# dCompass_7.net
KiCad netlist of a schematic drawn in EAGLE
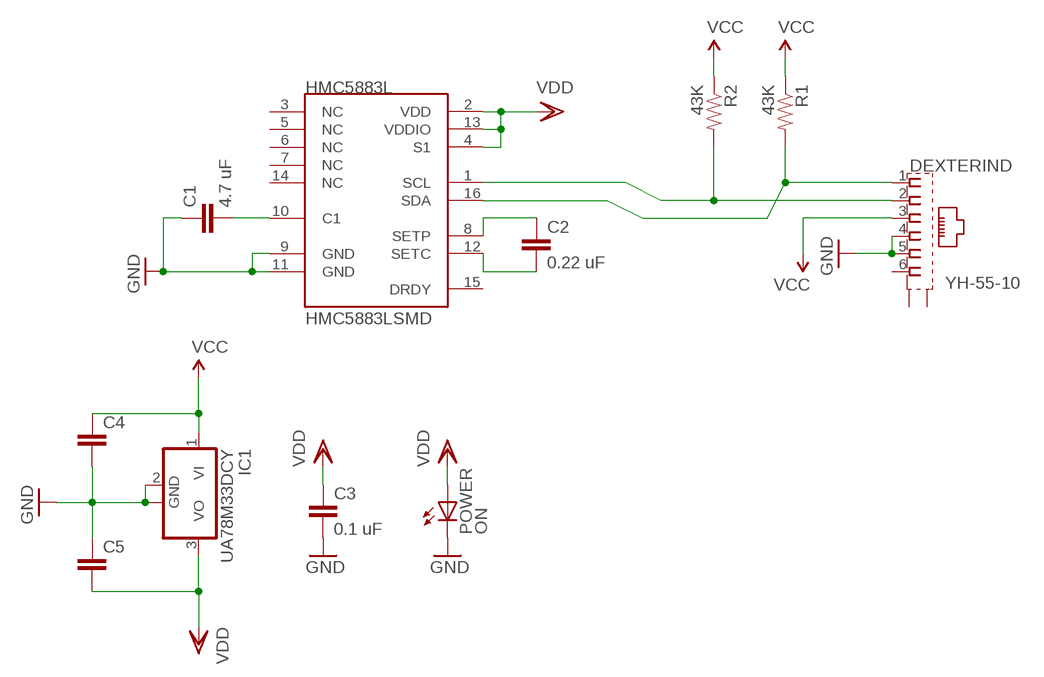
[diagram p0: schematic, sheet 1]

(export (version "E")
  (design (tool "Eeschema 10.0.6"))
  (components
    (comp (ref "C1")
      (value "4.7 uF")
      (footprint "eagle-import:0805")
      (libsource (lib "eagle-import") (part "CAP0805"))
    )
    (comp (ref "C2")
      (value "0.22 uF")
      (footprint "eagle-import:0805")
      (libsource (lib "eagle-import") (part "CAP0805"))
    )
    (comp (ref "C3")
      (value "0.1 uF")
      (footprint "eagle-import:0805")
      (libsource (lib "eagle-import") (part "CAP0805"))
    )
    (comp (ref "C4")
      (value "CAP0805")
      (footprint "eagle-import:0805")
      (libsource (lib "eagle-import") (part "CAP0805"))
    )
    (comp (ref "C5")
      (value "CAP0805")
      (footprint "eagle-import:0805")
      (libsource (lib "eagle-import") (part "CAP0805"))
    )
    (comp (ref "DEXTERIND")
      (value "YH-55-10")
      (footprint "eagle-import:YH-55-10")
      (libsource (lib "eagle-import") (part "YH-55-10"))
    )
    (comp (ref "HMC5883L")
      (value "HMC5883LSMD")
      (footprint "eagle-import:16LPCC")
      (libsource (lib "eagle-import") (part "HMC5883LSMD"))
    )
    (comp (ref "IC1")
      (value "UA78M33DCY")
      (footprint "eagle-import:SOT223")
      (libsource (lib "eagle-import") (part "UA78MDCY33"))
    )
    (comp (ref "POWER")
      (value "ON")
      (footprint "eagle-import:LED-1206")
      (libsource (lib "eagle-import") (part "LED1206"))
    )
    (comp (ref "R1")
      (value "43K")
      (footprint "eagle-import:0805")
      (libsource (lib "eagle-import") (part "RESISTOR0805-RES"))
    )
    (comp (ref "R2")
      (value "43K")
      (footprint "eagle-import:0805")
      (libsource (lib "eagle-import") (part "RESISTOR0805-RES"))
    )
  )
  (nets
    (net (code "1") (name "GND") (class "Default")
      (node (ref "C1") (pin "1") (pinfunction "1_1") (pintype "passive"))
      (node (ref "C3") (pin "2") (pinfunction "2_2") (pintype "passive"))
      (node (ref "C4") (pin "2") (pinfunction "2_2") (pintype "passive"))
      (node (ref "C5") (pin "1") (pinfunction "1_1") (pintype "passive"))
      (node (ref "DEXTERIND") (pin "4") (pinfunction "4_4") (pintype "passive"))
      (node (ref "DEXTERIND") (pin "5") (pinfunction "5_5") (pintype "passive"))
      (node (ref "HMC5883L") (pin "11") (pinfunction "GND_11") (pintype "bidirectional"))
      (node (ref "HMC5883L") (pin "9") (pinfunction "GND_9") (pintype "bidirectional"))
      (node (ref "IC1") (pin "2") (pinfunction "GND_2") (pintype "passive"))
      (node (ref "IC1") (pin "4") (pinfunction "GND_4") (pintype "passive"))
      (node (ref "POWER") (pin "C") (pinfunction "C_C") (pintype "passive"))
    )
    (net (code "2") (name "Net-(HMC5883L-C1)") (class "Default")
      (node (ref "C1") (pin "2") (pinfunction "2_2") (pintype "passive"))
      (node (ref "HMC5883L") (pin "10") (pinfunction "C1_10") (pintype "bidirectional"))
    )
    (net (code "3") (name "Net-(HMC5883L-SCL)") (class "Default")
      (node (ref "DEXTERIND") (pin "2") (pinfunction "2_2") (pintype "passive"))
      (node (ref "HMC5883L") (pin "1") (pinfunction "SCL_1") (pintype "bidirectional"))
      (node (ref "R2") (pin "2") (pinfunction "2_2") (pintype "passive"))
    )
    (net (code "4") (name "Net-(HMC5883L-SDA)") (class "Default")
      (node (ref "DEXTERIND") (pin "1") (pinfunction "1_1") (pintype "passive"))
      (node (ref "HMC5883L") (pin "16") (pinfunction "SDA_16") (pintype "bidirectional"))
      (node (ref "R1") (pin "2") (pinfunction "2_2") (pintype "passive"))
    )
    (net (code "5") (name "Net-(HMC5883L-SETC)") (class "Default")
      (node (ref "C2") (pin "2") (pinfunction "2_2") (pintype "passive"))
      (node (ref "HMC5883L") (pin "12") (pinfunction "SETC_12") (pintype "bidirectional"))
    )
    (net (code "6") (name "Net-(HMC5883L-SETP)") (class "Default")
      (node (ref "C2") (pin "1") (pinfunction "1_1") (pintype "passive"))
      (node (ref "HMC5883L") (pin "8") (pinfunction "SETP_8") (pintype "bidirectional"))
    )
    (net (code "7") (name "VCC") (class "Default")
      (node (ref "C4") (pin "1") (pinfunction "1_1") (pintype "passive"))
      (node (ref "DEXTERIND") (pin "3") (pinfunction "3_3") (pintype "passive"))
      (node (ref "IC1") (pin "1") (pinfunction "VI_1") (pintype "input"))
      (node (ref "R1") (pin "1") (pinfunction "1_1") (pintype "passive"))
      (node (ref "R2") (pin "1") (pinfunction "1_1") (pintype "passive"))
    )
    (net (code "8") (name "VDD") (class "Default")
      (node (ref "C3") (pin "1") (pinfunction "1_1") (pintype "passive"))
      (node (ref "C5") (pin "2") (pinfunction "2_2") (pintype "passive"))
      (node (ref "HMC5883L") (pin "13") (pinfunction "VDDIO_13") (pintype "bidirectional"))
      (node (ref "HMC5883L") (pin "2") (pinfunction "VDD_2") (pintype "bidirectional"))
      (node (ref "HMC5883L") (pin "4") (pinfunction "S1_4") (pintype "bidirectional"))
      (node (ref "IC1") (pin "3") (pinfunction "VO_3") (pintype "passive"))
      (node (ref "POWER") (pin "A") (pinfunction "A_A") (pintype "passive"))
    )
    (net (code "9") (name "unconnected-(DEXTERIND-Pad6)") (class "Default")
      (node (ref "DEXTERIND") (pin "6") (pinfunction "6_6") (pintype "passive"))
    )
    (net (code "10") (name "unconnected-(DEXTERIND-S-PadS1)") (class "Default")
      (node (ref "DEXTERIND") (pin "S1") (pinfunction "S_S1") (pintype "passive"))
    )
    (net (code "11") (name "unconnected-(DEXTERIND-S-PadS2)") (class "Default")
      (node (ref "DEXTERIND") (pin "S2") (pinfunction "S_S2") (pintype "passive"))
    )
    (net (code "12") (name "unconnected-(HMC5883L-DRDY-Pad15)") (class "Default")
      (node (ref "HMC5883L") (pin "15") (pinfunction "DRDY_15") (pintype "bidirectional"))
    )
    (net (code "13") (name "unconnected-(HMC5883L-NC-Pad3)") (class "Default")
      (node (ref "HMC5883L") (pin "3") (pinfunction "NC_3") (pintype "bidirectional"))
    )
    (net (code "14") (name "unconnected-(HMC5883L-NC-Pad5)") (class "Default")
      (node (ref "HMC5883L") (pin "5") (pinfunction "NC_5") (pintype "bidirectional"))
    )
    (net (code "15") (name "unconnected-(HMC5883L-NC-Pad6)") (class "Default")
      (node (ref "HMC5883L") (pin "6") (pinfunction "NC_6") (pintype "bidirectional"))
    )
    (net (code "16") (name "unconnected-(HMC5883L-NC-Pad7)") (class "Default")
      (node (ref "HMC5883L") (pin "7") (pinfunction "NC_7") (pintype "bidirectional"))
    )
    (net (code "17") (name "unconnected-(HMC5883L-NC-Pad14)") (class "Default")
      (node (ref "HMC5883L") (pin "14") (pinfunction "NC_14") (pintype "bidirectional"))
    )
  )
)
